# SD_Holder.net
KiCad netlist of a schematic drawn in Altium Designer
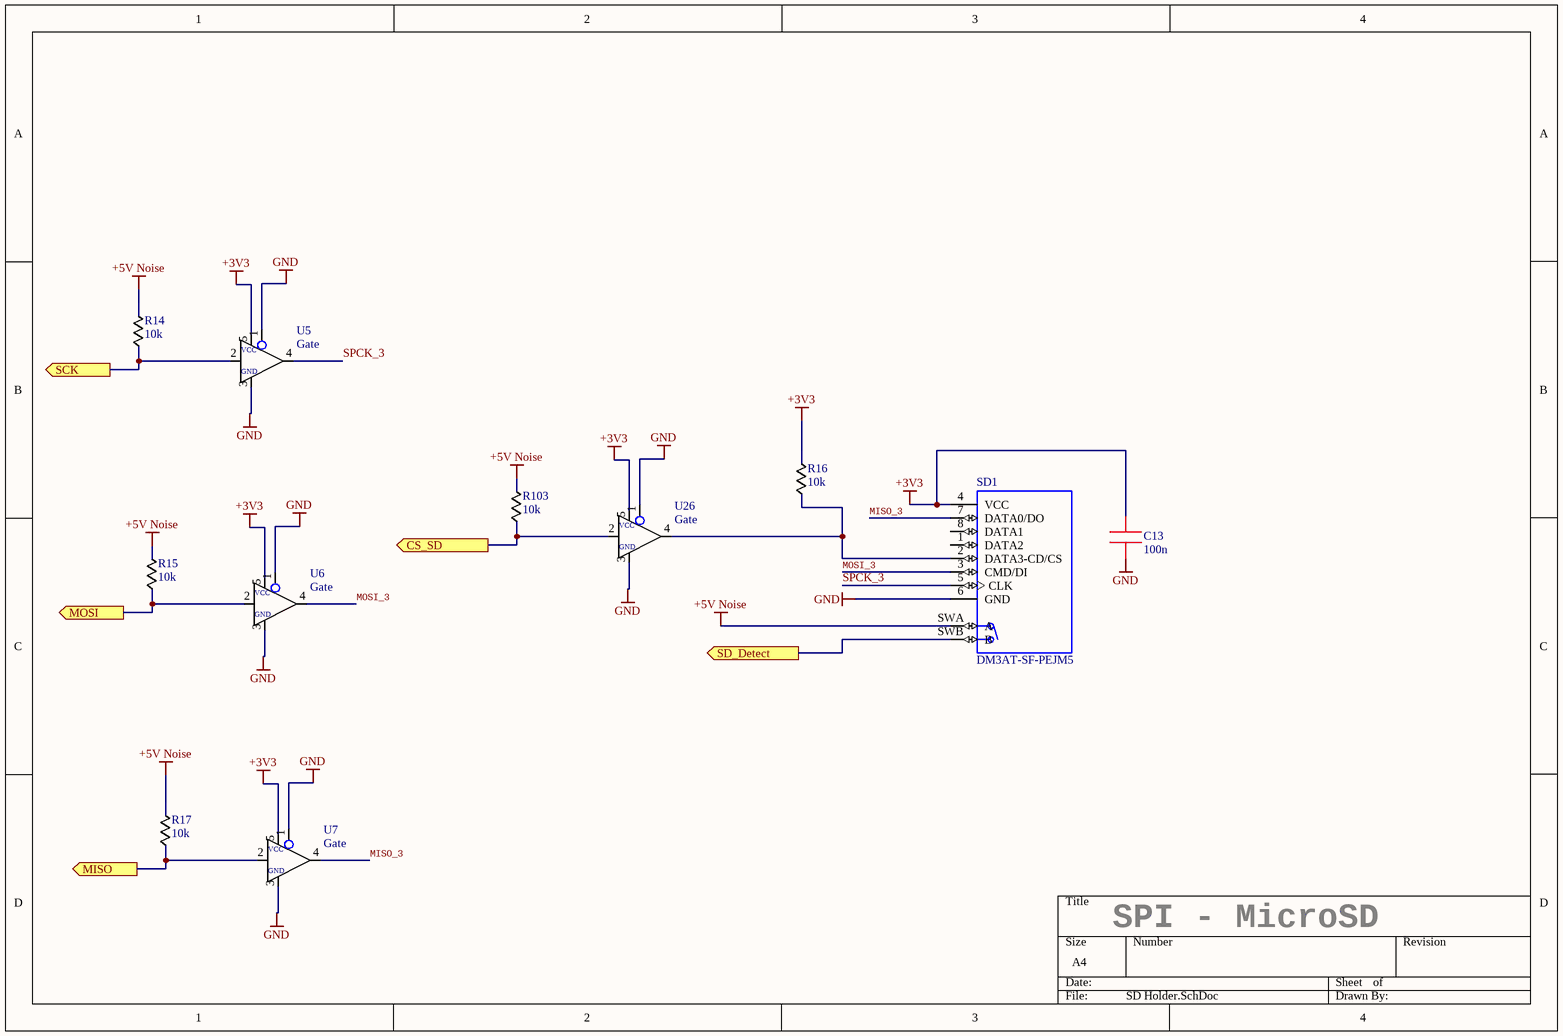
[diagram p0: SD Holder.SchDoc]

(export (version "E")
  (design (tool "Eeschema 10.0.6"))
  (components
    (comp (ref "C13")
      (value "100n")
      (footprint "0603")
      (description "CC0603KRX7R9BB104")
      (libsource (lib "kontr") (part "0603 CAP"))
    )
    (comp (ref "R14")
      (value "10k")
      (footprint "0603")
      (description "RT0603FRE0710KL")
      (libsource (lib "kontr") (part "0603 RES"))
    )
    (comp (ref "R15")
      (value "10k")
      (footprint "0603")
      (description "RT0603FRE0710KL")
      (libsource (lib "kontr") (part "0603 RES"))
    )
    (comp (ref "R16")
      (value "10k")
      (footprint "0603")
      (description "RT0603FRE0710KL")
      (libsource (lib "") (part "0603 RES_1"))
    )
    (comp (ref "R17")
      (value "10k")
      (footprint "0603")
      (description "RT0603FRE0710KL")
      (libsource (lib "kontr") (part "0603 RES"))
    )
    (comp (ref "R103")
      (value "10k")
      (footprint "0603")
      (description "RT0603FRE0710KL")
      (libsource (lib "kontr") (part "0603 RES"))
    )
    (comp (ref "SD1")
      (value "DM3AT-SF-PEJM5")
      (footprint "DM3AT-SF-PEJM5")
      (libsource (lib "kontr") (part "DM3AT-SF-PEJM5"))
    )
    (comp (ref "U5")
      (value "Gate")
      (footprint "SOT23 - 5 lead")
      (description "SN74LVC1G125DBVR")
      (libsource (lib "kontr") (part "Gate"))
    )
    (comp (ref "U6")
      (value "Gate")
      (footprint "SOT23 - 5 lead")
      (description "SN74LVC1G125DBVR")
      (libsource (lib "kontr") (part "Gate"))
    )
    (comp (ref "U7")
      (value "Gate")
      (footprint "SOT23 - 5 lead")
      (description "SN74LVC1G125DBVR")
      (libsource (lib "kontr") (part "Gate"))
    )
    (comp (ref "U26")
      (value "Gate")
      (footprint "SOT23 - 5 lead")
      (description "SN74LVC1G125DBVR")
      (libsource (lib "kontr") (part "Gate"))
    )
  )
  (nets
    (net (code "1") (name "+3V3") (class "Default")
      (node (ref "C13") (pin "2") (pinfunction "2_2") (pintype "passive"))
      (node (ref "R16") (pin "2") (pintype "passive"))
      (node (ref "SD1") (pin "4") (pinfunction "VCC_4") (pintype "power_in"))
      (node (ref "U26") (pin "5") (pinfunction "7_5") (pintype "passive"))
      (node (ref "U5") (pin "5") (pinfunction "7_5") (pintype "passive"))
      (node (ref "U6") (pin "5") (pinfunction "7_5") (pintype "passive"))
      (node (ref "U7") (pin "5") (pinfunction "7_5") (pintype "passive"))
    )
    (net (code "2") (name "+5V Noise") (class "Default")
      (node (ref "R103") (pin "2") (pintype "passive"))
      (node (ref "R14") (pin "2") (pintype "passive"))
      (node (ref "R15") (pin "2") (pintype "passive"))
      (node (ref "R17") (pin "2") (pintype "passive"))
      (node (ref "SD1") (pin "SWA") (pinfunction "A_SWA") (pintype "bidirectional"))
    )
    (net (code "3") (name "/CS_SD") (class "Default")
      (node (ref "R103") (pin "1") (pintype "passive"))
      (node (ref "U26") (pin "2") (pinfunction "7_2") (pintype "passive"))
    )
    (net (code "4") (name "/MISO") (class "Default")
      (node (ref "R17") (pin "1") (pintype "passive"))
      (node (ref "U7") (pin "2") (pinfunction "7_2") (pintype "passive"))
    )
    (net (code "5") (name "/MISO_3") (class "Default")
      (node (ref "SD1") (pin "7") (pinfunction "DATA0/DO_7") (pintype "bidirectional"))
      (node (ref "U7") (pin "4") (pinfunction "7_4") (pintype "passive"))
    )
    (net (code "6") (name "/MOSI") (class "Default")
      (node (ref "R15") (pin "1") (pintype "passive"))
      (node (ref "U6") (pin "2") (pinfunction "7_2") (pintype "passive"))
    )
    (net (code "7") (name "/MOSI_3") (class "Default")
      (node (ref "SD1") (pin "3") (pinfunction "CMD/DI_3") (pintype "bidirectional"))
      (node (ref "U6") (pin "4") (pinfunction "7_4") (pintype "passive"))
    )
    (net (code "8") (name "/SCK") (class "Default")
      (node (ref "R14") (pin "1") (pintype "passive"))
      (node (ref "U5") (pin "2") (pinfunction "7_2") (pintype "passive"))
    )
    (net (code "9") (name "/SD_Detect") (class "Default")
      (node (ref "SD1") (pin "SWB") (pinfunction "B_SWB") (pintype "bidirectional"))
    )
    (net (code "10") (name "/SPCK_3") (class "Default")
      (node (ref "SD1") (pin "5") (pinfunction "CLK_5") (pintype "bidirectional"))
      (node (ref "U5") (pin "4") (pinfunction "7_4") (pintype "passive"))
    )
    (net (code "11") (name "GND") (class "Default")
      (node (ref "C13") (pin "1") (pinfunction "1_1") (pintype "passive"))
      (node (ref "SD1") (pin "6") (pinfunction "GND_6") (pintype "power_in"))
      (node (ref "U26") (pin "1") (pinfunction "7_1") (pintype "passive"))
      (node (ref "U26") (pin "3") (pinfunction "7_3") (pintype "passive"))
      (node (ref "U5") (pin "1") (pinfunction "7_1") (pintype "passive"))
      (node (ref "U5") (pin "3") (pinfunction "7_3") (pintype "passive"))
      (node (ref "U6") (pin "1") (pinfunction "7_1") (pintype "passive"))
      (node (ref "U6") (pin "3") (pinfunction "7_3") (pintype "passive"))
      (node (ref "U7") (pin "1") (pinfunction "7_1") (pintype "passive"))
      (node (ref "U7") (pin "3") (pinfunction "7_3") (pintype "passive"))
    )
    (net (code "12") (name "Net-(SD1-DATA3-CD{slash}CS)") (class "Default")
      (node (ref "R16") (pin "1") (pintype "passive"))
      (node (ref "SD1") (pin "2") (pinfunction "DATA3-CD/CS_2") (pintype "bidirectional"))
      (node (ref "U26") (pin "4") (pinfunction "7_4") (pintype "passive"))
    )
    (net (code "13") (name "unconnected-(SD1-DATA1-Pad8)") (class "Default")
      (node (ref "SD1") (pin "8") (pinfunction "DATA1_8") (pintype "bidirectional"))
    )
    (net (code "14") (name "unconnected-(SD1-DATA2-Pad1)") (class "Default")
      (node (ref "SD1") (pin "1") (pinfunction "DATA2_1") (pintype "bidirectional"))
    )
  )
)
